# core_stm32.net
KiCad netlist of a schematic drawn in EAGLE
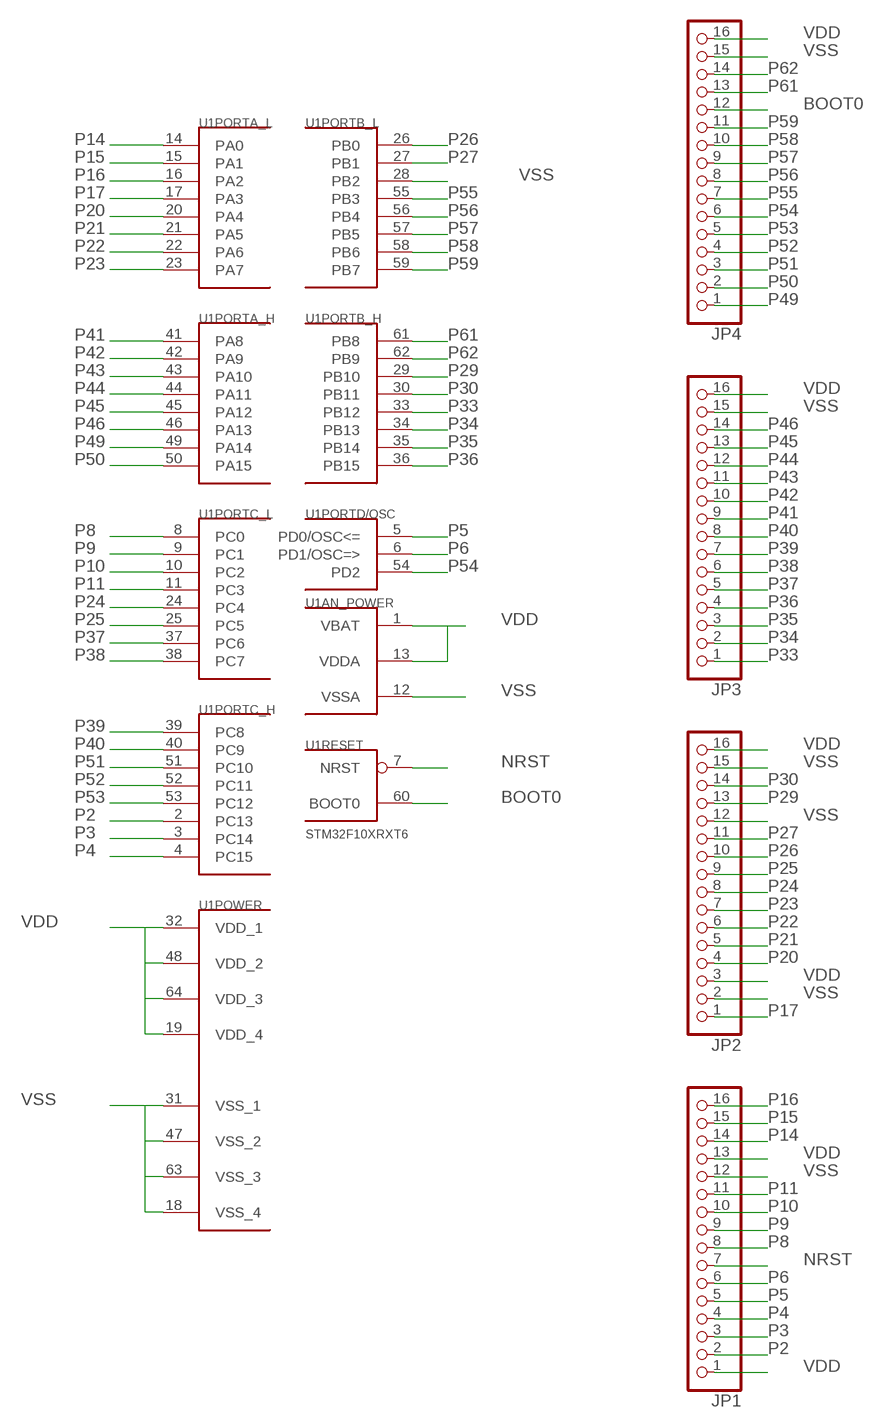
[diagram p0: schematic, sheet 1]

(export (version "E")
  (design (tool "Eeschema 10.0.6"))
  (components
    (comp (ref "JP1")
      (value "PINHD-1X16")
      (footprint "eagle-import:1X16")
      (libsource (lib "eagle-import") (part "PINHD-1X16"))
    )
    (comp (ref "JP2")
      (value "PINHD-1X16")
      (footprint "eagle-import:1X16")
      (libsource (lib "eagle-import") (part "PINHD-1X16"))
    )
    (comp (ref "JP3")
      (value "PINHD-1X16")
      (footprint "eagle-import:1X16")
      (libsource (lib "eagle-import") (part "PINHD-1X16"))
    )
    (comp (ref "JP4")
      (value "PINHD-1X16")
      (footprint "eagle-import:1X16")
      (libsource (lib "eagle-import") (part "PINHD-1X16"))
    )
    (comp (ref "U1")
      (value "STM32F10XRXT6")
      (footprint "eagle-import:TQFP64")
      (libsource (lib "eagle-import") (part "STM32F10XRXT6"))
    )
  )
  (nets
    (net (code "1") (name "/BOOT0") (class "Default")
      (node (ref "JP4") (pin "12") (pinfunction "12_12") (pintype "passive"))
      (node (ref "U1") (pin "60") (pinfunction "BOOT0_60") (pintype "input"))
    )
    (net (code "2") (name "/NRST") (class "Default")
      (node (ref "JP1") (pin "7") (pinfunction "7_7") (pintype "passive"))
      (node (ref "U1") (pin "7") (pinfunction "NRST_7") (pintype "input"))
    )
    (net (code "3") (name "/P2") (class "Default")
      (node (ref "JP1") (pin "2") (pinfunction "2_2") (pintype "passive"))
      (node (ref "U1") (pin "2") (pinfunction "PC13_2") (pintype "bidirectional"))
    )
    (net (code "4") (name "/P3") (class "Default")
      (node (ref "JP1") (pin "3") (pinfunction "3_3") (pintype "passive"))
      (node (ref "U1") (pin "3") (pinfunction "PC14_3") (pintype "bidirectional"))
    )
    (net (code "5") (name "/P4") (class "Default")
      (node (ref "JP1") (pin "4") (pinfunction "4_4") (pintype "passive"))
      (node (ref "U1") (pin "4") (pinfunction "PC15_4") (pintype "bidirectional"))
    )
    (net (code "6") (name "/P5") (class "Default")
      (node (ref "JP1") (pin "5") (pinfunction "5_5") (pintype "passive"))
      (node (ref "U1") (pin "5") (pinfunction "PD0/OSC<=_5") (pintype "bidirectional"))
    )
    (net (code "7") (name "/P6") (class "Default")
      (node (ref "JP1") (pin "6") (pinfunction "6_6") (pintype "passive"))
      (node (ref "U1") (pin "6") (pinfunction "PD1/OSC=>_6") (pintype "bidirectional"))
    )
    (net (code "8") (name "/P8") (class "Default")
      (node (ref "JP1") (pin "8") (pinfunction "8_8") (pintype "passive"))
      (node (ref "U1") (pin "8") (pinfunction "PC0_8") (pintype "bidirectional"))
    )
    (net (code "9") (name "/P9") (class "Default")
      (node (ref "JP1") (pin "9") (pinfunction "9_9") (pintype "passive"))
      (node (ref "U1") (pin "9") (pinfunction "PC1_9") (pintype "bidirectional"))
    )
    (net (code "10") (name "/P10") (class "Default")
      (node (ref "JP1") (pin "10") (pinfunction "10_10") (pintype "passive"))
      (node (ref "U1") (pin "10") (pinfunction "PC2_10") (pintype "bidirectional"))
    )
    (net (code "11") (name "/P11") (class "Default")
      (node (ref "JP1") (pin "11") (pinfunction "11_11") (pintype "passive"))
      (node (ref "U1") (pin "11") (pinfunction "PC3_11") (pintype "bidirectional"))
    )
    (net (code "12") (name "/P14") (class "Default")
      (node (ref "JP1") (pin "14") (pinfunction "14_14") (pintype "passive"))
      (node (ref "U1") (pin "14") (pinfunction "PA0_14") (pintype "bidirectional"))
    )
    (net (code "13") (name "/P15") (class "Default")
      (node (ref "JP1") (pin "15") (pinfunction "15_15") (pintype "passive"))
      (node (ref "U1") (pin "15") (pinfunction "PA1_15") (pintype "bidirectional"))
    )
    (net (code "14") (name "/P16") (class "Default")
      (node (ref "JP1") (pin "16") (pinfunction "16_16") (pintype "passive"))
      (node (ref "U1") (pin "16") (pinfunction "PA2_16") (pintype "bidirectional"))
    )
    (net (code "15") (name "/P17") (class "Default")
      (node (ref "JP2") (pin "1") (pinfunction "1_1") (pintype "passive"))
      (node (ref "U1") (pin "17") (pinfunction "PA3_17") (pintype "bidirectional"))
    )
    (net (code "16") (name "/P20") (class "Default")
      (node (ref "JP2") (pin "4") (pinfunction "4_4") (pintype "passive"))
      (node (ref "U1") (pin "20") (pinfunction "PA4_20") (pintype "bidirectional"))
    )
    (net (code "17") (name "/P21") (class "Default")
      (node (ref "JP2") (pin "5") (pinfunction "5_5") (pintype "passive"))
      (node (ref "U1") (pin "21") (pinfunction "PA5_21") (pintype "bidirectional"))
    )
    (net (code "18") (name "/P22") (class "Default")
      (node (ref "JP2") (pin "6") (pinfunction "6_6") (pintype "passive"))
      (node (ref "U1") (pin "22") (pinfunction "PA6_22") (pintype "bidirectional"))
    )
    (net (code "19") (name "/P23") (class "Default")
      (node (ref "JP2") (pin "7") (pinfunction "7_7") (pintype "passive"))
      (node (ref "U1") (pin "23") (pinfunction "PA7_23") (pintype "bidirectional"))
    )
    (net (code "20") (name "/P24") (class "Default")
      (node (ref "JP2") (pin "8") (pinfunction "8_8") (pintype "passive"))
      (node (ref "U1") (pin "24") (pinfunction "PC4_24") (pintype "bidirectional"))
    )
    (net (code "21") (name "/P25") (class "Default")
      (node (ref "JP2") (pin "9") (pinfunction "9_9") (pintype "passive"))
      (node (ref "U1") (pin "25") (pinfunction "PC5_25") (pintype "bidirectional"))
    )
    (net (code "22") (name "/P26") (class "Default")
      (node (ref "JP2") (pin "10") (pinfunction "10_10") (pintype "passive"))
      (node (ref "U1") (pin "26") (pinfunction "PB0_26") (pintype "bidirectional"))
    )
    (net (code "23") (name "/P27") (class "Default")
      (node (ref "JP2") (pin "11") (pinfunction "11_11") (pintype "passive"))
      (node (ref "U1") (pin "27") (pinfunction "PB1_27") (pintype "bidirectional"))
    )
    (net (code "24") (name "/P29") (class "Default")
      (node (ref "JP2") (pin "13") (pinfunction "13_13") (pintype "passive"))
      (node (ref "U1") (pin "29") (pinfunction "PB10_29") (pintype "bidirectional"))
    )
    (net (code "25") (name "/P30") (class "Default")
      (node (ref "JP2") (pin "14") (pinfunction "14_14") (pintype "passive"))
      (node (ref "U1") (pin "30") (pinfunction "PB11_30") (pintype "bidirectional"))
    )
    (net (code "26") (name "/P33") (class "Default")
      (node (ref "JP3") (pin "1") (pinfunction "1_1") (pintype "passive"))
      (node (ref "U1") (pin "33") (pinfunction "PB12_33") (pintype "bidirectional"))
    )
    (net (code "27") (name "/P34") (class "Default")
      (node (ref "JP3") (pin "2") (pinfunction "2_2") (pintype "passive"))
      (node (ref "U1") (pin "34") (pinfunction "PB13_34") (pintype "bidirectional"))
    )
    (net (code "28") (name "/P35") (class "Default")
      (node (ref "JP3") (pin "3") (pinfunction "3_3") (pintype "passive"))
      (node (ref "U1") (pin "35") (pinfunction "PB14_35") (pintype "bidirectional"))
    )
    (net (code "29") (name "/P36") (class "Default")
      (node (ref "JP3") (pin "4") (pinfunction "4_4") (pintype "passive"))
      (node (ref "U1") (pin "36") (pinfunction "PB15_36") (pintype "bidirectional"))
    )
    (net (code "30") (name "/P37") (class "Default")
      (node (ref "JP3") (pin "5") (pinfunction "5_5") (pintype "passive"))
      (node (ref "U1") (pin "37") (pinfunction "PC6_37") (pintype "bidirectional"))
    )
    (net (code "31") (name "/P38") (class "Default")
      (node (ref "JP3") (pin "6") (pinfunction "6_6") (pintype "passive"))
      (node (ref "U1") (pin "38") (pinfunction "PC7_38") (pintype "bidirectional"))
    )
    (net (code "32") (name "/P39") (class "Default")
      (node (ref "JP3") (pin "7") (pinfunction "7_7") (pintype "passive"))
      (node (ref "U1") (pin "39") (pinfunction "PC8_39") (pintype "bidirectional"))
    )
    (net (code "33") (name "/P40") (class "Default")
      (node (ref "JP3") (pin "8") (pinfunction "8_8") (pintype "passive"))
      (node (ref "U1") (pin "40") (pinfunction "PC9_40") (pintype "bidirectional"))
    )
    (net (code "34") (name "/P41") (class "Default")
      (node (ref "JP3") (pin "9") (pinfunction "9_9") (pintype "passive"))
      (node (ref "U1") (pin "41") (pinfunction "PA8_41") (pintype "bidirectional"))
    )
    (net (code "35") (name "/P42") (class "Default")
      (node (ref "JP3") (pin "10") (pinfunction "10_10") (pintype "passive"))
      (node (ref "U1") (pin "42") (pinfunction "PA9_42") (pintype "bidirectional"))
    )
    (net (code "36") (name "/P43") (class "Default")
      (node (ref "JP3") (pin "11") (pinfunction "11_11") (pintype "passive"))
      (node (ref "U1") (pin "43") (pinfunction "PA10_43") (pintype "bidirectional"))
    )
    (net (code "37") (name "/P44") (class "Default")
      (node (ref "JP3") (pin "12") (pinfunction "12_12") (pintype "passive"))
      (node (ref "U1") (pin "44") (pinfunction "PA11_44") (pintype "bidirectional"))
    )
    (net (code "38") (name "/P45") (class "Default")
      (node (ref "JP3") (pin "13") (pinfunction "13_13") (pintype "passive"))
      (node (ref "U1") (pin "45") (pinfunction "PA12_45") (pintype "bidirectional"))
    )
    (net (code "39") (name "/P46") (class "Default")
      (node (ref "JP3") (pin "14") (pinfunction "14_14") (pintype "passive"))
      (node (ref "U1") (pin "46") (pinfunction "PA13_46") (pintype "bidirectional"))
    )
    (net (code "40") (name "/P49") (class "Default")
      (node (ref "JP4") (pin "1") (pinfunction "1_1") (pintype "passive"))
      (node (ref "U1") (pin "49") (pinfunction "PA14_49") (pintype "bidirectional"))
    )
    (net (code "41") (name "/P50") (class "Default")
      (node (ref "JP4") (pin "2") (pinfunction "2_2") (pintype "passive"))
      (node (ref "U1") (pin "50") (pinfunction "PA15_50") (pintype "bidirectional"))
    )
    (net (code "42") (name "/P51") (class "Default")
      (node (ref "JP4") (pin "3") (pinfunction "3_3") (pintype "passive"))
      (node (ref "U1") (pin "51") (pinfunction "PC10_51") (pintype "bidirectional"))
    )
    (net (code "43") (name "/P52") (class "Default")
      (node (ref "JP4") (pin "4") (pinfunction "4_4") (pintype "passive"))
      (node (ref "U1") (pin "52") (pinfunction "PC11_52") (pintype "bidirectional"))
    )
    (net (code "44") (name "/P53") (class "Default")
      (node (ref "JP4") (pin "5") (pinfunction "5_5") (pintype "passive"))
      (node (ref "U1") (pin "53") (pinfunction "PC12_53") (pintype "bidirectional"))
    )
    (net (code "45") (name "/P54") (class "Default")
      (node (ref "JP4") (pin "6") (pinfunction "6_6") (pintype "passive"))
      (node (ref "U1") (pin "54") (pinfunction "PD2_54") (pintype "bidirectional"))
    )
    (net (code "46") (name "/P55") (class "Default")
      (node (ref "JP4") (pin "7") (pinfunction "7_7") (pintype "passive"))
      (node (ref "U1") (pin "55") (pinfunction "PB3_55") (pintype "bidirectional"))
    )
    (net (code "47") (name "/P56") (class "Default")
      (node (ref "JP4") (pin "8") (pinfunction "8_8") (pintype "passive"))
      (node (ref "U1") (pin "56") (pinfunction "PB4_56") (pintype "bidirectional"))
    )
    (net (code "48") (name "/P57") (class "Default")
      (node (ref "JP4") (pin "9") (pinfunction "9_9") (pintype "passive"))
      (node (ref "U1") (pin "57") (pinfunction "PB5_57") (pintype "bidirectional"))
    )
    (net (code "49") (name "/P58") (class "Default")
      (node (ref "JP4") (pin "10") (pinfunction "10_10") (pintype "passive"))
      (node (ref "U1") (pin "58") (pinfunction "PB6_58") (pintype "bidirectional"))
    )
    (net (code "50") (name "/P59") (class "Default")
      (node (ref "JP4") (pin "11") (pinfunction "11_11") (pintype "passive"))
      (node (ref "U1") (pin "59") (pinfunction "PB7_59") (pintype "bidirectional"))
    )
    (net (code "51") (name "/P61") (class "Default")
      (node (ref "JP4") (pin "13") (pinfunction "13_13") (pintype "passive"))
      (node (ref "U1") (pin "61") (pinfunction "PB8_61") (pintype "bidirectional"))
    )
    (net (code "52") (name "/P62") (class "Default")
      (node (ref "JP4") (pin "14") (pinfunction "14_14") (pintype "passive"))
      (node (ref "U1") (pin "62") (pinfunction "PB9_62") (pintype "bidirectional"))
    )
    (net (code "53") (name "/VDD") (class "Default")
      (node (ref "JP1") (pin "1") (pinfunction "1_1") (pintype "passive"))
      (node (ref "JP1") (pin "13") (pinfunction "13_13") (pintype "passive"))
      (node (ref "JP2") (pin "16") (pinfunction "16_16") (pintype "passive"))
      (node (ref "JP2") (pin "3") (pinfunction "3_3") (pintype "passive"))
      (node (ref "JP3") (pin "16") (pinfunction "16_16") (pintype "passive"))
      (node (ref "JP4") (pin "16") (pinfunction "16_16") (pintype "passive"))
      (node (ref "U1") (pin "1") (pinfunction "VBAT_1") (pintype "power_in"))
      (node (ref "U1") (pin "13") (pinfunction "VDDA_13") (pintype "power_in"))
      (node (ref "U1") (pin "19") (pinfunction "VDD_4_19") (pintype "power_in"))
      (node (ref "U1") (pin "32") (pinfunction "VDD_1_32") (pintype "power_in"))
      (node (ref "U1") (pin "48") (pinfunction "VDD_2_48") (pintype "power_in"))
      (node (ref "U1") (pin "64") (pinfunction "VDD_3_64") (pintype "power_in"))
    )
    (net (code "54") (name "/VSS") (class "Default")
      (node (ref "JP1") (pin "12") (pinfunction "12_12") (pintype "passive"))
      (node (ref "JP2") (pin "12") (pinfunction "12_12") (pintype "passive"))
      (node (ref "JP2") (pin "15") (pinfunction "15_15") (pintype "passive"))
      (node (ref "JP2") (pin "2") (pinfunction "2_2") (pintype "passive"))
      (node (ref "JP3") (pin "15") (pinfunction "15_15") (pintype "passive"))
      (node (ref "JP4") (pin "15") (pinfunction "15_15") (pintype "passive"))
      (node (ref "U1") (pin "12") (pinfunction "VSSA_12") (pintype "power_in"))
      (node (ref "U1") (pin "18") (pinfunction "VSS_4_18") (pintype "power_in"))
      (node (ref "U1") (pin "28") (pinfunction "PB2_28") (pintype "bidirectional"))
      (node (ref "U1") (pin "31") (pinfunction "VSS_1_31") (pintype "power_in"))
      (node (ref "U1") (pin "47") (pinfunction "VSS_2_47") (pintype "power_in"))
      (node (ref "U1") (pin "63") (pinfunction "VSS_3_63") (pintype "power_in"))
    )
  )
)
